# STM32_IO.net
KiCad netlist of a schematic drawn in Altium Designer
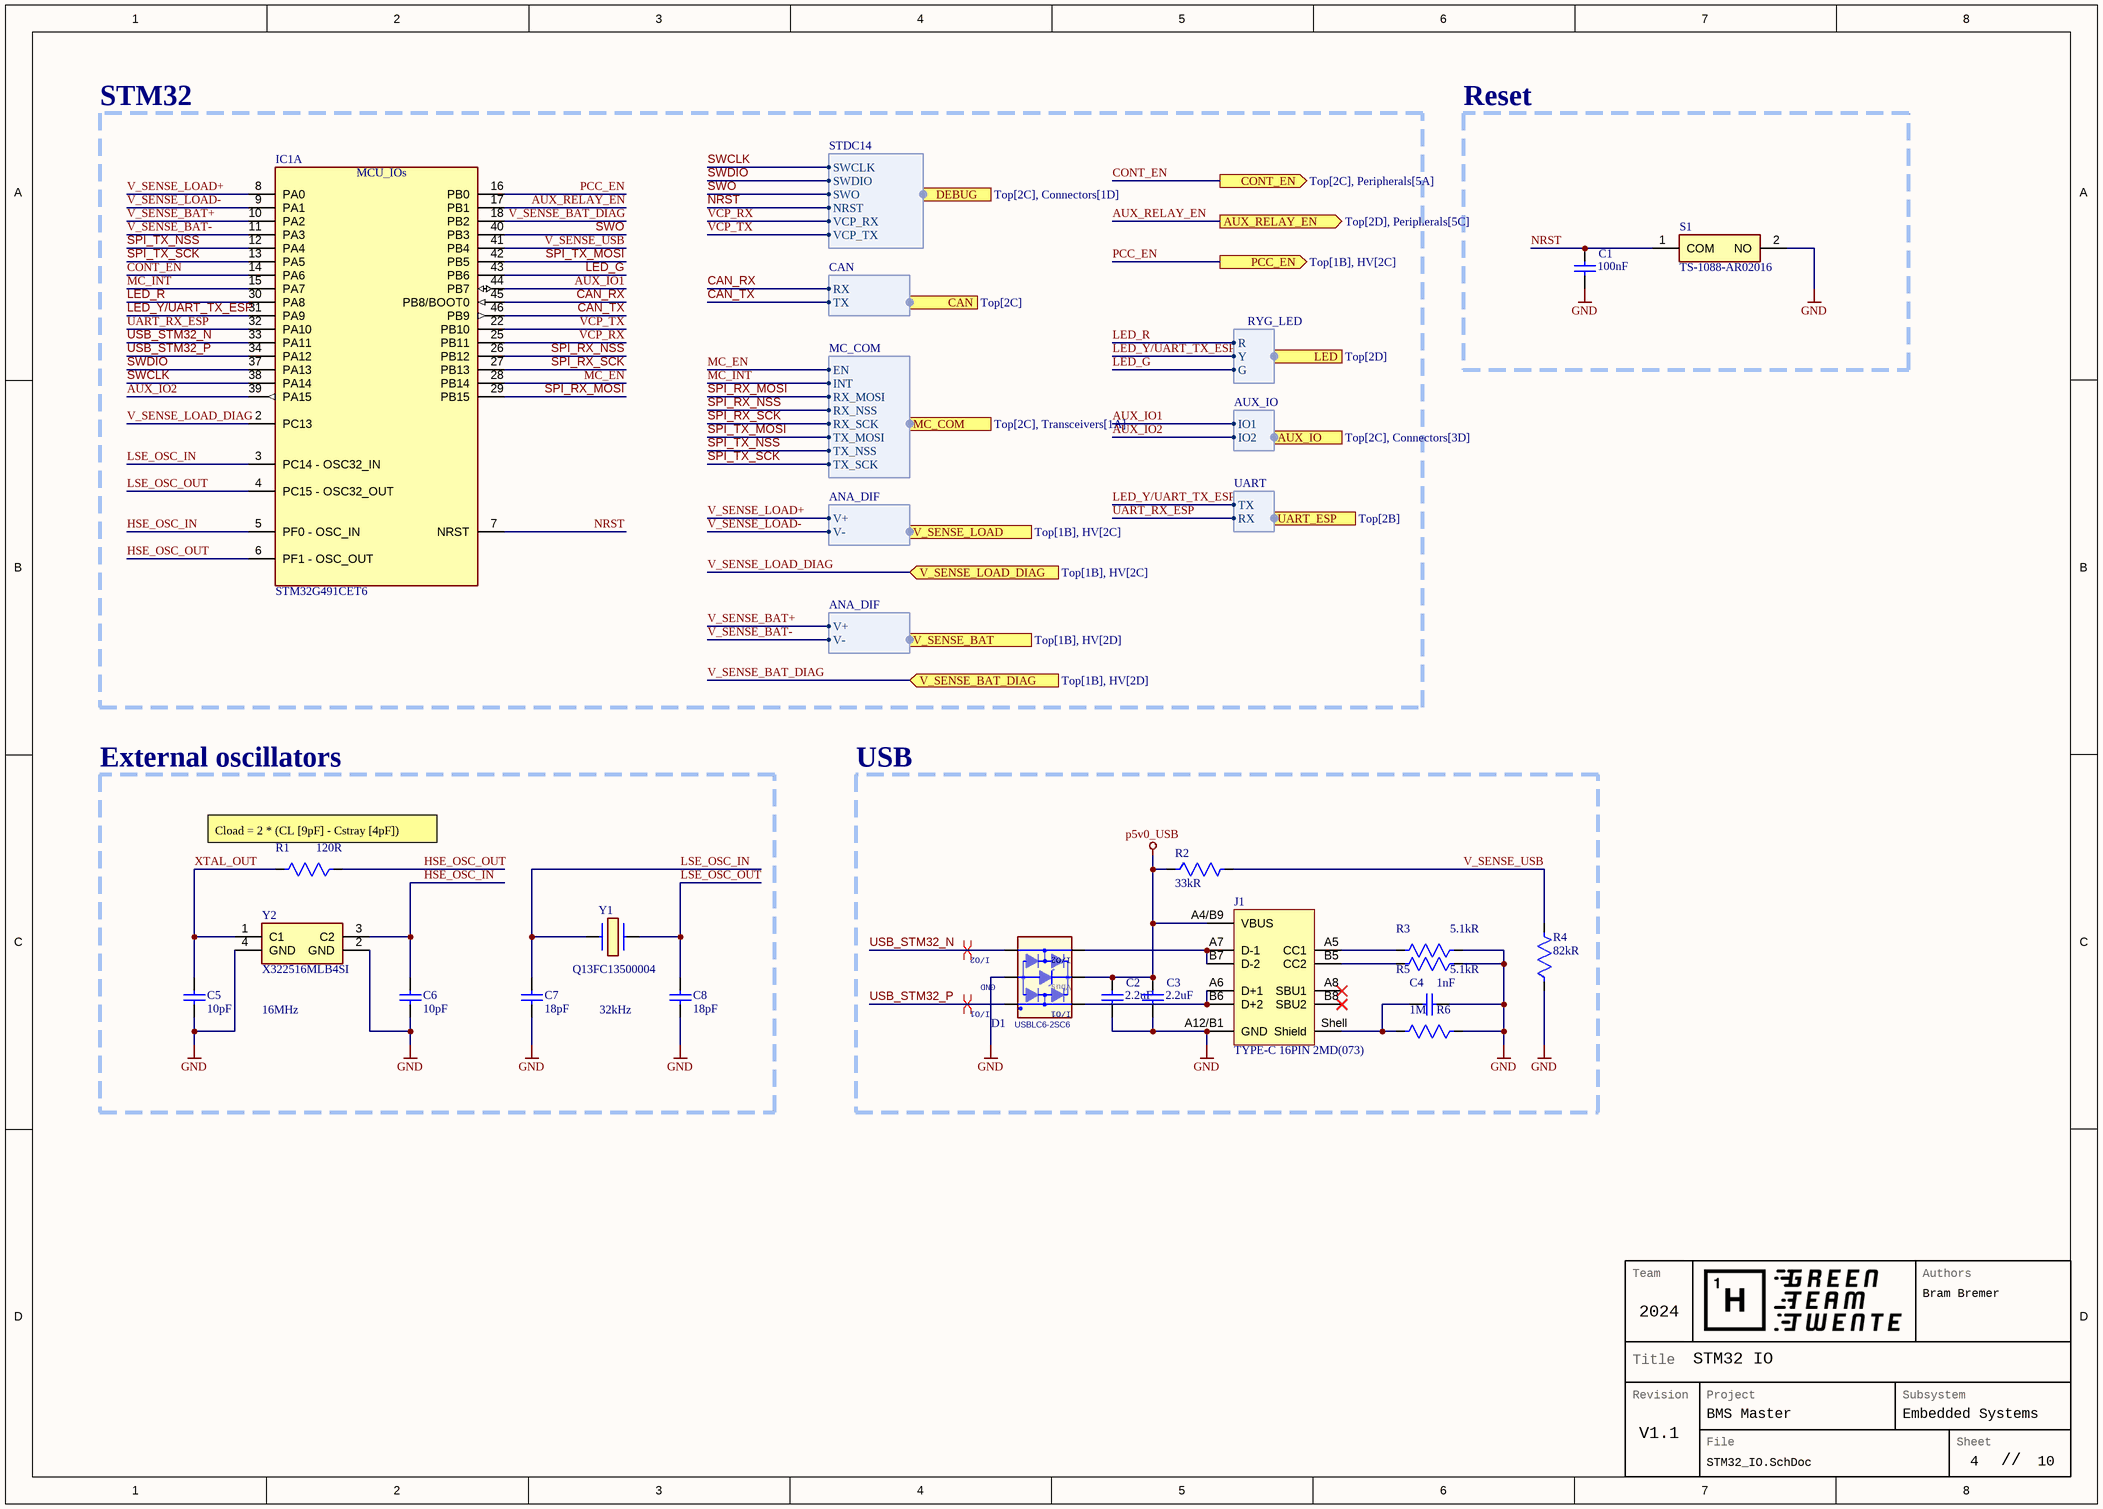
[diagram p0: STM32_IO.SchDoc]

(export (version "E")
  (design (tool "Eeschema 10.0.6"))
  (components
    (comp (ref "C1")
      (value "100nF")
      (footprint "WCAP-CSGP_0402_L1W0.5H0.5")
      (description "GTT Standard 0402 non-polarized capacitor")
      (fields (field (name "JLCPCB PART #") "C1525") (field (name "Comment") "CAP 0402 100nF X7R"))
      (libsource (lib "Green Team Twente") (part "CAP_NONPOL_GENERIC"))
    )
    (comp (ref "C2")
      (value "2.2uF")
      (footprint "WCAP-CSGP_0603_L1.6W0.8H0.8_Reflow")
      (description "GTT Standard 0603 non-polarized capacitor")
      (fields (field (name "JLCPCB PART #") "C23630") (field (name "Comment") "CAP 0603 2.2uF X7R"))
      (libsource (lib "Green Team Twente") (part "CAP_NONPOL_GENERIC"))
    )
    (comp (ref "C3")
      (value "2.2uF")
      (footprint "WCAP-CSGP_0603_L1.6W0.8H0.8_Reflow")
      (description "GTT Standard 0603 non-polarized capacitor")
      (fields (field (name "JLCPCB PART #") "C23630") (field (name "Comment") "CAP 0603 2.2uF X7R"))
      (libsource (lib "Green Team Twente") (part "CAP_NONPOL_GENERIC"))
    )
    (comp (ref "C4")
      (value "1nF")
      (footprint "WCAP-CSGP_1206_L3.2W1.6H1.15")
      (description "GTT Standard 1206 non-polarized capacitor")
      (fields (field (name "JLCPCB PART #") "C9196") (field (name "Comment") "CAP 1206 1nF X7R"))
      (libsource (lib "Green Team Twente") (part "CAP_NONPOL_GENERIC"))
    )
    (comp (ref "C5")
      (value "10pF")
      (footprint "WCAP-CSGP_0402_L1W0.5H0.5")
      (description "GTT Standard 0402 non-polarized capacitor")
      (fields (field (name "JLCPCB PART #") "C32949") (field (name "Comment") "CAP 0402 10pF X7R"))
      (libsource (lib "Green Team Twente") (part "CAP_NONPOL_GENERIC"))
    )
    (comp (ref "C6")
      (value "10pF")
      (footprint "WCAP-CSGP_0402_L1W0.5H0.5")
      (description "GTT Standard 0402 non-polarized capacitor")
      (fields (field (name "JLCPCB PART #") "C32949") (field (name "Comment") "CAP 0402 10pF X7R"))
      (libsource (lib "Green Team Twente") (part "CAP_NONPOL_GENERIC"))
    )
    (comp (ref "C7")
      (value "18pF")
      (footprint "WCAP-CSGP_0402_L1W0.5H0.5")
      (description "GTT Standard 0402 non-polarized capacitor")
      (fields (field (name "JLCPCB PART #") "C1549") (field (name "Comment") "CAP 0402 18pF X7R"))
      (libsource (lib "Green Team Twente") (part "CAP_NONPOL_GENERIC"))
    )
    (comp (ref "C8")
      (value "18pF")
      (footprint "WCAP-CSGP_0402_L1W0.5H0.5")
      (description "GTT Standard 0402 non-polarized capacitor")
      (fields (field (name "JLCPCB PART #") "C1549") (field (name "Comment") "CAP 0402 18pF X7R"))
      (libsource (lib "Green Team Twente") (part "CAP_NONPOL_GENERIC"))
    )
    (comp (ref "D1")
      (value "USBLC6-2SC6")
      (footprint "ST_SOT23-6L")
      (libsource (lib "Green Team Twente") (part "USBLC6-2SC6"))
    )
    (comp (ref "IC1")
      (value "STM32G491CET6")
      (footprint "QFP50P900X900X160-48N")
      (description "ARM Microcontrollers - MCU Mainstream Arm Cortex-M4+ MCU 170MHz with 512Kbytes of Flash memory")
      (fields (field (name "MOUSER PART NUMBER") "511-STM32G491CET6"))
      (libsource (lib "Green Team Twente") (part "STM32G491CET6"))
    )
    (comp (ref "J1")
      (value "TYPE-C 16PIN 2MD(073)")
      (footprint "629722000214")
      (description "WR-USB 2.0 Type C, Receptacle, Horizontal, SMT")
      (fields
        (field (name "MANUFACTURER") "Wurth Elektronik")
        (field (name "MANUFACTURER PART NUMBER") "629722000214")
      )
      (libsource (lib "Green Team Twente") (part "USB-C"))
    )
    (comp (ref "R1")
      (value "120R")
      (footprint "FP0402")
      (description "GTT Standard 0402 Resistor")
      (fields (field (name "TOLERANCE") "1%") (field (name "POWER") "62.5mW"))
      (libsource (lib "Green Team Twente") (part "RES_GENERIC"))
    )
    (comp (ref "R2")
      (value "33kR")
      (footprint "FP0402")
      (description "GTT Standard 0402 Resistor")
      (fields (field (name "TOLERANCE") "1%") (field (name "POWER") "62.5mW"))
      (libsource (lib "Green Team Twente") (part "RES_GENERIC"))
    )
    (comp (ref "R3")
      (value "5.1kR")
      (footprint "FP0402")
      (description "GTT Standard 0402 Resistor")
      (fields (field (name "TOLERANCE") "1%") (field (name "POWER") "62.5mW"))
      (libsource (lib "Green Team Twente") (part "RES_GENERIC"))
    )
    (comp (ref "R4")
      (value "82kR")
      (footprint "RES_SM0603_YAGEORC_N")
      (description "GTT Standard 0603 Resistor")
      (fields (field (name "POWER") "62.5mW") (field (name "TOLERANCE") "1%"))
      (libsource (lib "Green Team Twente") (part "RES_GENERIC"))
    )
    (comp (ref "R5")
      (value "5.1kR")
      (footprint "FP0402")
      (description "GTT Standard 0402 Resistor")
      (fields (field (name "TOLERANCE") "1%") (field (name "POWER") "62.5mW"))
      (libsource (lib "Green Team Twente") (part "RES_GENERIC"))
    )
    (comp (ref "R6")
      (value "1M")
      (footprint "RES_SM1206_YAGEORC_N")
      (description "GTT Standard 1206 Resistor")
      (fields (field (name "TOLERANCE") "1%") (field (name "POWER") "62.5mW"))
      (libsource (lib "Green Team Twente") (part "RES_GENERIC"))
    )
    (comp (ref "S1")
      (value "TS-1088-AR02016")
      (footprint "TS1088AR02016")
      (description "Switch")
      (libsource (lib "FlexBMS_lib") (part "TS-1088-AR02016"))
    )
    (comp (ref "Y1")
      (value "Q13FC13500004")
      (footprint "Q13FC1350000400")
      (description "Crystal or Oscillator")
      (fields (field (name "MANUFACTURER_PART_NUMBER") "Q13FC1350000400"))
      (libsource (lib "FlexBMS_lib") (part "Q13FC13500004"))
    )
    (comp (ref "Y2")
      (value "X322516MLB4SI")
      (footprint "X322516MLB4SI")
      (description "Crystal or Oscillator")
      (libsource (lib "FlexBMS_lib") (part "X322516MLB4SI"))
    )
  )
  (nets
    (net (code "8") (name "/AUX_IO1") (class "Default")
      (node (ref "IC1") (pin "44") (pinfunction "PB7_44") (pintype "bidirectional"))
    )
    (net (code "9") (name "/AUX_IO2") (class "Default")
      (node (ref "IC1") (pin "39") (pinfunction "PA15_39") (pintype "output"))
    )
    (net (code "10") (name "/AUX_RELAY_EN") (class "Default")
      (node (ref "IC1") (pin "17") (pinfunction "PB1_17") (pintype "passive"))
    )
    (net (code "11") (name "/CAN_RX") (class "Default")
      (node (ref "IC1") (pin "45") (pinfunction "PB8/BOOT0_45") (pintype "input"))
    )
    (net (code "12") (name "/CAN_TX") (class "Default")
      (node (ref "IC1") (pin "46") (pinfunction "PB9_46") (pintype "output"))
    )
    (net (code "13") (name "/CONT_EN") (class "Default")
      (node (ref "IC1") (pin "14") (pinfunction "PA6_14") (pintype "passive"))
    )
    (net (code "14") (name "/HSE_OSC_IN") (class "Default")
      (node (ref "C6") (pin "2") (pinfunction "2_2") (pintype "passive"))
      (node (ref "IC1") (pin "5") (pinfunction "PF0_-_OSC_IN_5") (pintype "passive"))
      (node (ref "Y2") (pin "3") (pinfunction "C2_3") (pintype "passive"))
    )
    (net (code "15") (name "/HSE_OSC_OUT") (class "Default")
      (node (ref "IC1") (pin "6") (pinfunction "PF1_-_OSC_OUT_6") (pintype "passive"))
      (node (ref "R1") (pin "1") (pinfunction "1_1") (pintype "passive"))
    )
    (net (code "16") (name "/LED_G") (class "Default")
      (node (ref "IC1") (pin "43") (pinfunction "PB6_43") (pintype "passive"))
    )
    (net (code "17") (name "/LED_R") (class "Default")
      (node (ref "IC1") (pin "30") (pinfunction "PA8_30") (pintype "passive"))
    )
    (net (code "18") (name "/LED_Y{slash}UART_TX_ESP") (class "Default")
      (node (ref "IC1") (pin "31") (pinfunction "PA9_31") (pintype "passive"))
    )
    (net (code "19") (name "/LSE_OSC_IN") (class "Default")
      (node (ref "C7") (pin "2") (pinfunction "2_2") (pintype "passive"))
      (node (ref "IC1") (pin "3") (pinfunction "PC14_-_OSC32_IN_3") (pintype "passive"))
      (node (ref "Y1") (pin "2") (pinfunction "CRYSTAL_2_2") (pintype "passive"))
    )
    (net (code "20") (name "/LSE_OSC_OUT") (class "Default")
      (node (ref "C8") (pin "2") (pinfunction "2_2") (pintype "passive"))
      (node (ref "IC1") (pin "4") (pinfunction "PC15_-_OSC32_OUT_4") (pintype "passive"))
      (node (ref "Y1") (pin "1") (pinfunction "CRYSTAL_1_1") (pintype "passive"))
    )
    (net (code "21") (name "/MC_EN") (class "Default")
      (node (ref "IC1") (pin "28") (pinfunction "PB14_28") (pintype "passive"))
    )
    (net (code "22") (name "/MC_INT") (class "Default")
      (node (ref "IC1") (pin "15") (pinfunction "PA7_15") (pintype "passive"))
    )
    (net (code "23") (name "/NRST") (class "Default")
      (node (ref "C1") (pin "2") (pinfunction "2_2") (pintype "passive"))
      (node (ref "IC1") (pin "7") (pinfunction "NRST_7") (pintype "passive"))
      (node (ref "S1") (pin "1") (pinfunction "COM_1") (pintype "passive"))
    )
    (net (code "24") (name "/PCC_EN") (class "Default")
      (node (ref "IC1") (pin "16") (pinfunction "PB0_16") (pintype "passive"))
    )
    (net (code "25") (name "/SPI_RX_MOSI") (class "Default")
      (node (ref "IC1") (pin "29") (pinfunction "PB15_29") (pintype "passive"))
    )
    (net (code "26") (name "/SPI_RX_NSS") (class "Default")
      (node (ref "IC1") (pin "26") (pinfunction "PB12_26") (pintype "passive"))
    )
    (net (code "27") (name "/SPI_RX_SCK") (class "Default")
      (node (ref "IC1") (pin "27") (pinfunction "PB13_27") (pintype "passive"))
    )
    (net (code "28") (name "/SPI_TX_MOSI") (class "Default")
      (node (ref "IC1") (pin "42") (pinfunction "PB5_42") (pintype "passive"))
    )
    (net (code "29") (name "/SPI_TX_NSS") (class "Default")
      (node (ref "IC1") (pin "12") (pinfunction "PA4_12") (pintype "passive"))
    )
    (net (code "30") (name "/SPI_TX_SCK") (class "Default")
      (node (ref "IC1") (pin "13") (pinfunction "PA5_13") (pintype "passive"))
    )
    (net (code "31") (name "/SWCLK") (class "Default")
      (node (ref "IC1") (pin "38") (pinfunction "PA14_38") (pintype "passive"))
    )
    (net (code "32") (name "/SWDIO") (class "Default")
      (node (ref "IC1") (pin "37") (pinfunction "PA13_37") (pintype "passive"))
    )
    (net (code "33") (name "/SWO") (class "Default")
      (node (ref "IC1") (pin "40") (pinfunction "PB3_40") (pintype "passive"))
    )
    (net (code "34") (name "/UART_RX_ESP") (class "Default")
      (node (ref "IC1") (pin "32") (pinfunction "PA10_32") (pintype "passive"))
    )
    (net (code "35") (name "/USB_STM32_N") (class "Default")
      (node (ref "D1") (pin "3") (pinfunction "I/O2_3") (pintype "passive"))
      (node (ref "IC1") (pin "33") (pinfunction "PA11_33") (pintype "passive"))
    )
    (net (code "36") (name "/USB_STM32_P") (class "Default")
      (node (ref "D1") (pin "1") (pinfunction "I/O1_1") (pintype "passive"))
      (node (ref "IC1") (pin "34") (pinfunction "PA12_34") (pintype "passive"))
    )
    (net (code "37") (name "/VCP_RX") (class "Default")
      (node (ref "IC1") (pin "25") (pinfunction "PB11_25") (pintype "passive"))
    )
    (net (code "38") (name "/VCP_TX") (class "Default")
      (node (ref "IC1") (pin "22") (pinfunction "PB10_22") (pintype "passive"))
    )
    (net (code "39") (name "/V_SENSE_BAT+") (class "Default")
      (node (ref "IC1") (pin "10") (pinfunction "PA2_10") (pintype "passive"))
    )
    (net (code "40") (name "/V_SENSE_BAT-") (class "Default")
      (node (ref "IC1") (pin "11") (pinfunction "PA3_11") (pintype "passive"))
    )
    (net (code "41") (name "/V_SENSE_BAT_DIAG") (class "Default")
      (node (ref "IC1") (pin "18") (pinfunction "PB2_18") (pintype "passive"))
    )
    (net (code "42") (name "/V_SENSE_LOAD+") (class "Default")
      (node (ref "IC1") (pin "8") (pinfunction "PA0_8") (pintype "passive"))
    )
    (net (code "43") (name "/V_SENSE_LOAD-") (class "Default")
      (node (ref "IC1") (pin "9") (pinfunction "PA1_9") (pintype "passive"))
    )
    (net (code "44") (name "/V_SENSE_LOAD_DIAG") (class "Default")
      (node (ref "IC1") (pin "2") (pinfunction "PC13_2") (pintype "passive"))
    )
    (net (code "45") (name "/V_SENSE_USB") (class "Default")
      (node (ref "IC1") (pin "41") (pinfunction "PB4_41") (pintype "passive"))
      (node (ref "R2") (pin "2") (pinfunction "2_2") (pintype "passive"))
      (node (ref "R4") (pin "2") (pinfunction "2_2") (pintype "passive"))
    )
    (net (code "46") (name "/XTAL_OUT") (class "Default")
      (node (ref "C5") (pin "2") (pinfunction "2_2") (pintype "passive"))
      (node (ref "R1") (pin "2") (pinfunction "2_2") (pintype "passive"))
      (node (ref "Y2") (pin "1") (pinfunction "C1_1") (pintype "passive"))
    )
    (net (code "54") (name "GND") (class "Default")
      (node (ref "C1") (pin "1") (pinfunction "1_1") (pintype "passive"))
      (node (ref "C2") (pin "1") (pinfunction "1_1") (pintype "passive"))
      (node (ref "C3") (pin "1") (pinfunction "1_1") (pintype "passive"))
      (node (ref "C4") (pin "2") (pinfunction "2_2") (pintype "passive"))
      (node (ref "C5") (pin "1") (pinfunction "1_1") (pintype "passive"))
      (node (ref "C6") (pin "1") (pinfunction "1_1") (pintype "passive"))
      (node (ref "C7") (pin "1") (pinfunction "1_1") (pintype "passive"))
      (node (ref "C8") (pin "1") (pinfunction "1_1") (pintype "passive"))
      (node (ref "D1") (pin "2") (pinfunction "GND_2") (pintype "passive"))
      (node (ref "J1") (pin "A12/B1") (pinfunction "GND_A12/B1") (pintype "passive"))
      (node (ref "R3") (pin "1") (pinfunction "1_1") (pintype "passive"))
      (node (ref "R4") (pin "1") (pinfunction "1_1") (pintype "passive"))
      (node (ref "R5") (pin "1") (pinfunction "1_1") (pintype "passive"))
      (node (ref "R6") (pin "1") (pinfunction "1_1") (pintype "passive"))
      (node (ref "S1") (pin "2") (pinfunction "NO_2") (pintype "passive"))
      (node (ref "Y2") (pin "2") (pinfunction "GND_2") (pintype "passive"))
      (node (ref "Y2") (pin "4") (pinfunction "GND_4") (pintype "passive"))
    )
    (net (code "55") (name "Net-(D1-I{slash}O1+)") (class "Default")
      (node (ref "D1") (pin "6") (pinfunction "I/O1+_6") (pintype "passive"))
      (node (ref "J1") (pin "A6") (pinfunction "D+1_A6") (pintype "passive"))
      (node (ref "J1") (pin "B6") (pinfunction "D+2_B6") (pintype "passive"))
    )
    (net (code "56") (name "Net-(D1-I{slash}O2+)") (class "Default")
      (node (ref "D1") (pin "4") (pinfunction "I/O2+_4") (pintype "passive"))
      (node (ref "J1") (pin "A7") (pinfunction "D-1_A7") (pintype "passive"))
      (node (ref "J1") (pin "B7") (pinfunction "D-2_B7") (pintype "passive"))
    )
    (net (code "57") (name "Net-(J1-CC1)") (class "Default")
      (node (ref "J1") (pin "A5") (pinfunction "CC1_A5") (pintype "passive"))
      (node (ref "R3") (pin "2") (pinfunction "2_2") (pintype "passive"))
    )
    (net (code "58") (name "Net-(J1-CC2)") (class "Default")
      (node (ref "J1") (pin "B5") (pinfunction "CC2_B5") (pintype "passive"))
      (node (ref "R5") (pin "2") (pinfunction "2_2") (pintype "passive"))
    )
    (net (code "59") (name "Net-(J1-Shield)") (class "Default")
      (node (ref "C4") (pin "1") (pinfunction "1_1") (pintype "passive"))
      (node (ref "J1") (pin "Shell") (pinfunction "Shield_Shell") (pintype "passive"))
      (node (ref "R6") (pin "2") (pinfunction "2_2") (pintype "passive"))
    )
    (net (code "60") (name "p5v0_USB") (class "Default")
      (node (ref "C2") (pin "2") (pinfunction "2_2") (pintype "passive"))
      (node (ref "C3") (pin "2") (pinfunction "2_2") (pintype "passive"))
      (node (ref "D1") (pin "5") (pinfunction "Vbus_5") (pintype "passive"))
      (node (ref "J1") (pin "A4/B9") (pinfunction "VBUS_A4/B9") (pintype "passive"))
      (node (ref "R2") (pin "1") (pinfunction "1_1") (pintype "passive"))
    )
    (net (code "61") (name "unconnected-(J1-SBU1-PadA8)") (class "Default")
      (node (ref "J1") (pin "A8") (pinfunction "SBU1_A8") (pintype "passive+no_connect"))
    )
    (net (code "62") (name "unconnected-(J1-SBU2-PadB8)") (class "Default")
      (node (ref "J1") (pin "B8") (pinfunction "SBU2_B8") (pintype "passive+no_connect"))
    )
  )
)
